# MCU_main.net
KiCad netlist of a schematic drawn in Altium Designer
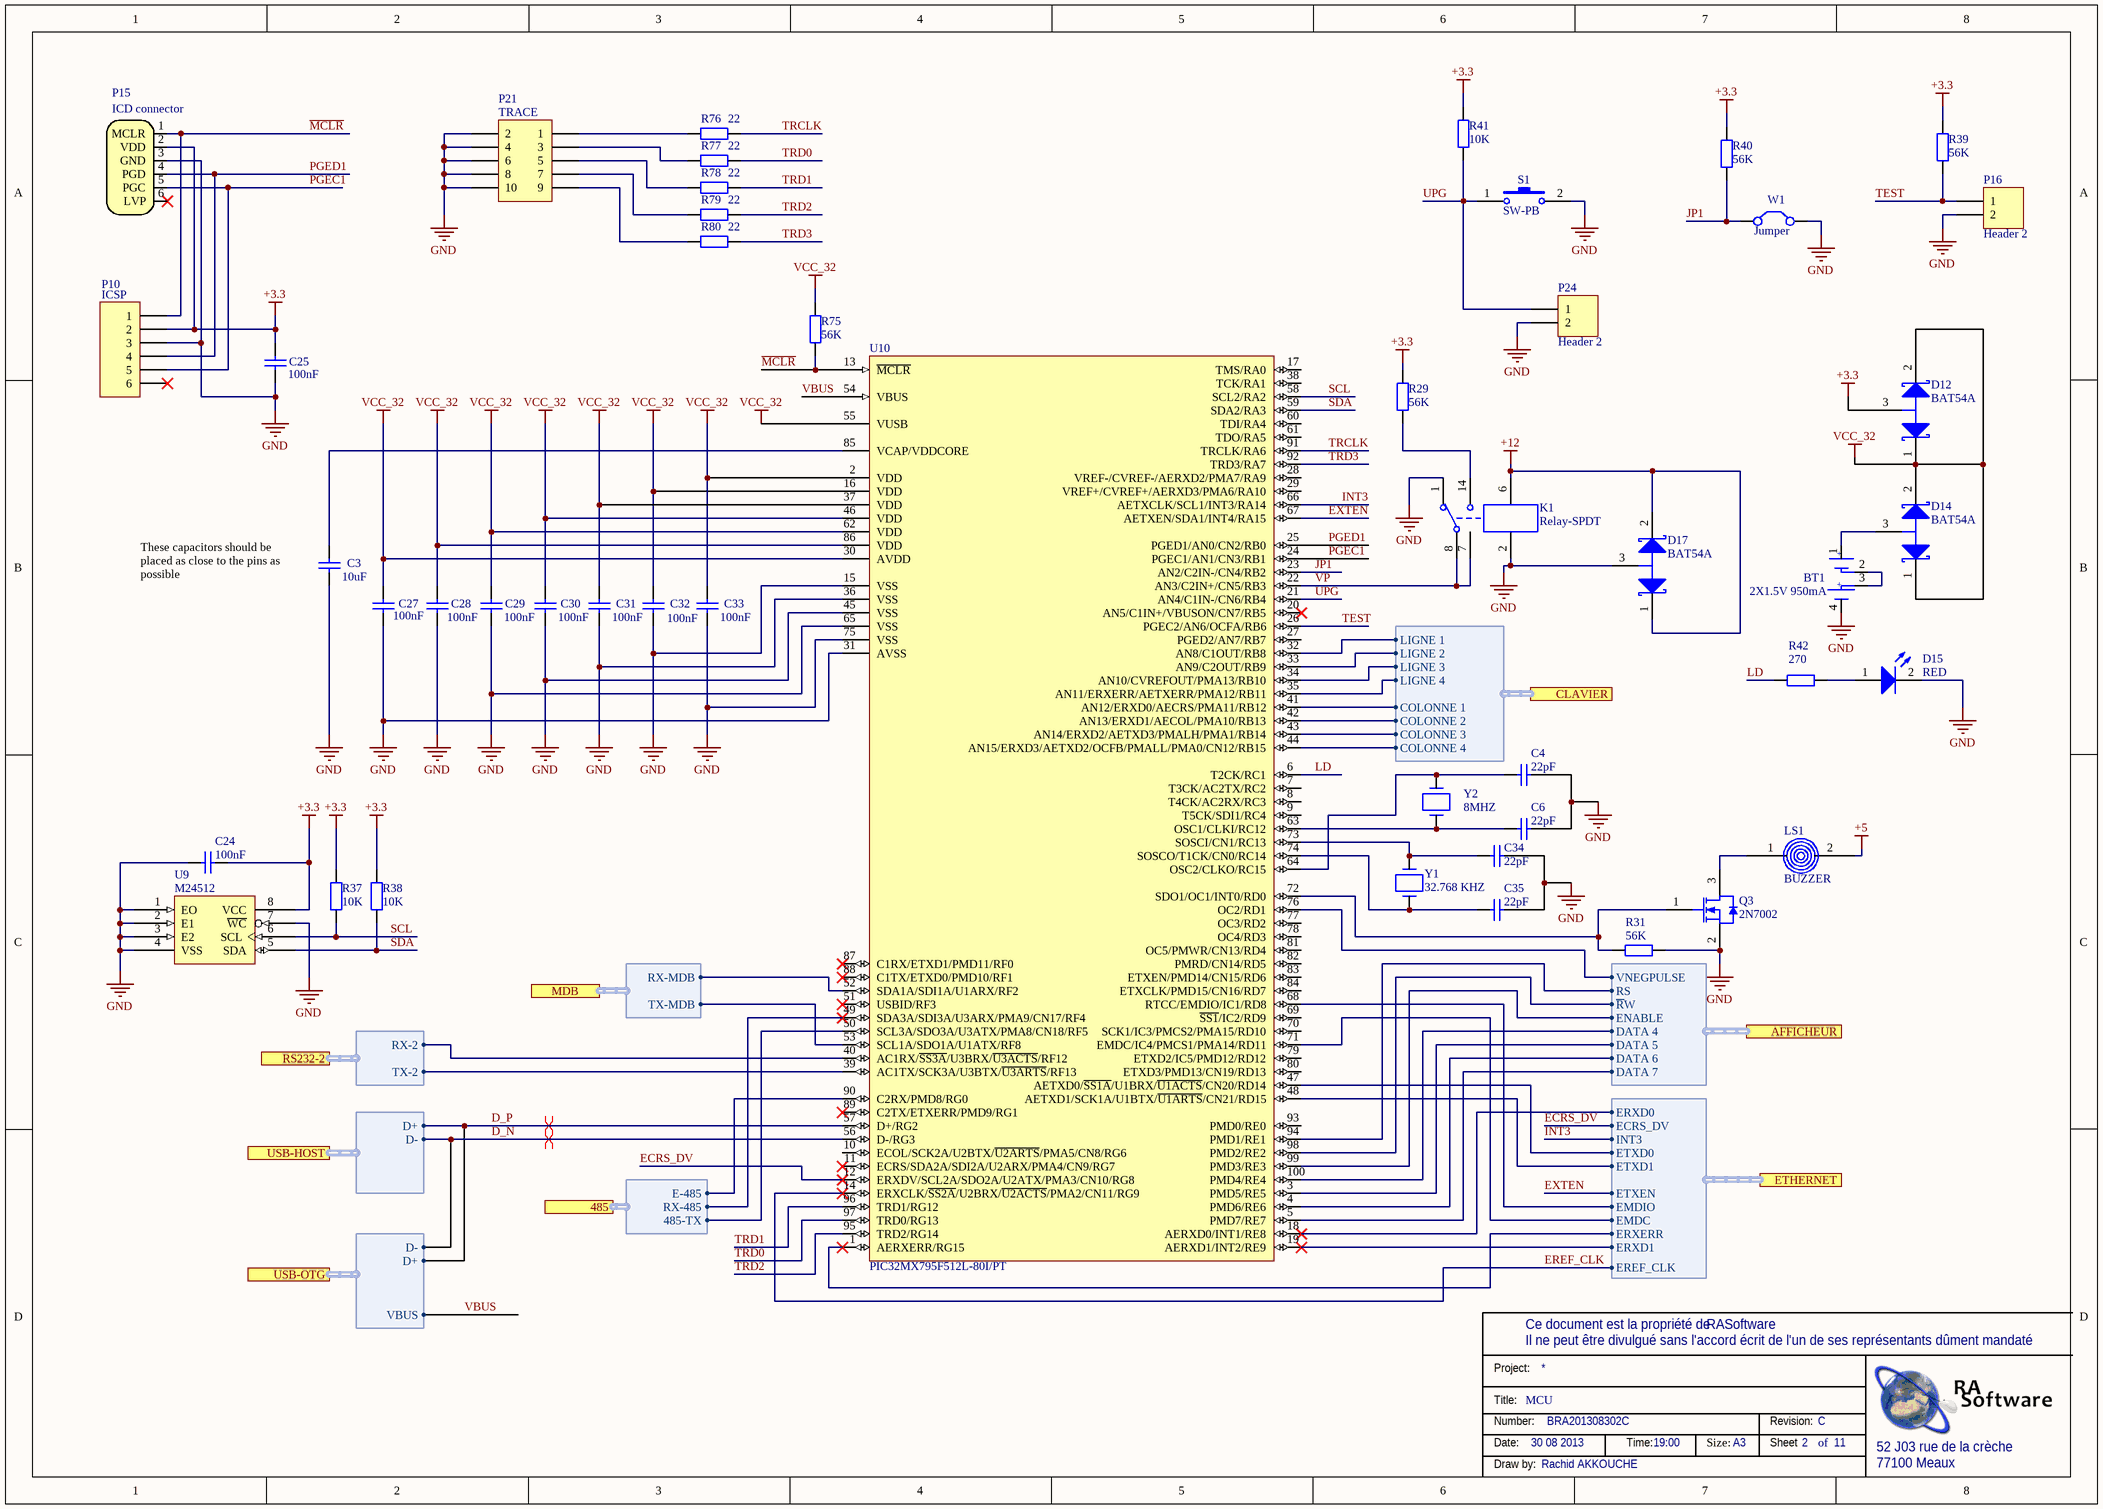
[diagram p0: MCU main.SchDoc]

(export (version "E")
  (design (tool "Eeschema 10.0.6"))
  (components
    (comp (ref "BT1")
      (value "2X1.5V 950mA")
      (footprint "Support Pile 1023")
      (libsource (lib "UTIL_Library") (part "BATTERYX2"))
    )
    (comp (ref "C3")
      (value "10uF")
      (footprint "c0805")
      (description "Capacitor")
      (fields
        (field (name "MANUFACTURER") "YAGEO")
        (field (name "MANUFACTURER PART NUMBER") "CC0805KKX5R5BB106")
      )
      (libsource (lib "BRA") (part "Cap 0805 1uF"))
    )
    (comp (ref "C4")
      (value "22pF")
      (footprint "C0805")
      (description "Capacitor")
      (fields
        (field (name "MANUFACTURER") "YAGEO")
        (field (name "MANUFACTURER PART NUMBER") "CC0805JRNPO9BN220")
      )
      (libsource (lib "BRA") (part "Cap 0805 22pF"))
    )
    (comp (ref "C6")
      (value "22pF")
      (footprint "C0805")
      (description "Capacitor")
      (fields
        (field (name "MANUFACTURER") "YAGEO")
        (field (name "MANUFACTURER PART NUMBER") "CC0805JRNPO9BN220")
      )
      (libsource (lib "BRA") (part "Cap 0805 22pF"))
    )
    (comp (ref "C24")
      (value "100nF")
      (footprint "C0805")
      (description "Capacitor")
      (fields
        (field (name "MANUFACTURER") "MULTICOMP")
        (field (name "MANUFACTURER PART NUMBER") "MCCA000296")
      )
      (libsource (lib "BRA") (part "Cap 0805 100nF"))
    )
    (comp (ref "C25")
      (value "100nF")
      (footprint "C0805")
      (description "Capacitor")
      (fields
        (field (name "MANUFACTURER") "MULTICOMP")
        (field (name "MANUFACTURER PART NUMBER") "MCCA000296")
      )
      (libsource (lib "BRA") (part "Cap 0805 100nF"))
    )
    (comp (ref "C27")
      (value "100nF")
      (footprint "C0805")
      (description "Capacitor")
      (fields
        (field (name "MANUFACTURER") "MULTICOMP")
        (field (name "MANUFACTURER PART NUMBER") "MCCA000296")
      )
      (libsource (lib "BRA") (part "Cap 0805 100nF"))
    )
    (comp (ref "C28")
      (value "100nF")
      (footprint "C0805")
      (description "Capacitor")
      (fields
        (field (name "MANUFACTURER") "MULTICOMP")
        (field (name "MANUFACTURER PART NUMBER") "MCCA000296")
      )
      (libsource (lib "BRA") (part "Cap 0805 100nF"))
    )
    (comp (ref "C29")
      (value "100nF")
      (footprint "C0805")
      (description "Capacitor")
      (fields
        (field (name "MANUFACTURER") "MULTICOMP")
        (field (name "MANUFACTURER PART NUMBER") "MCCA000296")
      )
      (libsource (lib "BRA") (part "Cap 0805 100nF"))
    )
    (comp (ref "C30")
      (value "100nF")
      (footprint "C0805")
      (description "Capacitor")
      (fields
        (field (name "MANUFACTURER") "MULTICOMP")
        (field (name "MANUFACTURER PART NUMBER") "MCCA000296")
      )
      (libsource (lib "BRA") (part "Cap 0805 100nF"))
    )
    (comp (ref "C31")
      (value "100nF")
      (footprint "C0805")
      (description "Capacitor")
      (fields
        (field (name "MANUFACTURER") "MULTICOMP")
        (field (name "MANUFACTURER PART NUMBER") "MCCA000296")
      )
      (libsource (lib "BRA") (part "Cap 0805 100nF"))
    )
    (comp (ref "C32")
      (value "100nF")
      (footprint "C0805")
      (description "Capacitor")
      (fields
        (field (name "MANUFACTURER") "MULTICOMP")
        (field (name "MANUFACTURER PART NUMBER") "MCCA000296")
      )
      (libsource (lib "BRA") (part "Cap 0805 100nF"))
    )
    (comp (ref "C33")
      (value "100nF")
      (footprint "C0805")
      (description "Capacitor")
      (fields
        (field (name "MANUFACTURER") "MULTICOMP")
        (field (name "MANUFACTURER PART NUMBER") "MCCA000296")
      )
      (libsource (lib "BRA") (part "Cap 0805 100nF"))
    )
    (comp (ref "C34")
      (value "22pF")
      (footprint "C0805")
      (description "Capacitor")
      (fields
        (field (name "MANUFACTURER") "YAGEO")
        (field (name "MANUFACTURER PART NUMBER") "CC0805JRNPO9BN220")
      )
      (libsource (lib "BRA") (part "Cap 0805 22pF"))
    )
    (comp (ref "C35")
      (value "22pF")
      (footprint "C0805")
      (description "Capacitor")
      (fields
        (field (name "MANUFACTURER") "YAGEO")
        (field (name "MANUFACTURER PART NUMBER") "CC0805JRNPO9BN220")
      )
      (libsource (lib "BRA") (part "Cap 0805 22pF"))
    )
    (comp (ref "D12")
      (value "BAT54A")
      (footprint "SOT23")
      (description "Schottky Barrier Double Diode")
      (fields (field (name "MANUFACTURER") "FAIRCHILD SEMICONDUCTOR"))
      (libsource (lib "Philips Discrete Diode - Schottky") (part "BAT54A"))
    )
    (comp (ref "D14")
      (value "BAT54A")
      (footprint "SOT23")
      (description "Schottky Barrier Double Diode")
      (fields (field (name "MANUFACTURER") "FAIRCHILD SEMICONDUCTOR"))
      (libsource (lib "Philips Discrete Diode - Schottky") (part "BAT54A"))
    )
    (comp (ref "D15")
      (value "HSMH-C190")
      (footprint "SYLANN:0603-LEDR")
      (description "Surface Mount Chip LED, Red")
      (fields
        (field (name "MANUFACTURER") "AVAGO TECHNOLOGIES")
        (field (name "MANUFACTURER PART NUMBER") "HSMH-C190.")
        (field (name "COULEUR") "RED")
        (field (name "LONGUEUR/HAUTEUR") "1.6")
      )
      (libsource (lib "Avago Optoelectronic LED") (part "HSMH-C190"))
    )
    (comp (ref "D17")
      (value "BAT54A")
      (footprint "SOT23")
      (description "Schottky Barrier Double Diode")
      (fields (field (name "MANUFACTURER") "FAIRCHILD SEMICONDUCTOR"))
      (libsource (lib "Philips Discrete Diode - Schottky") (part "BAT54A"))
    )
    (comp (ref "K1")
      (value "Relay-SPDT")
      (footprint "RELE-REED-PVX6012")
      (description "Single-Pole Dual-Throw Relay")
      (fields
        (field (name "MANUFACTURER") "STANDEXMEDER")
        (field (name "MANUFACTURER PART NUMBER") "DIP12-1C90-51L")
        (field (name "PUBLISHER") "Altium Limited")
      )
      (libsource (lib "MAIN BOARD CERES_1") (part "Relay-SPDT"))
    )
    (comp (ref "LS1")
      (value "BUZZER")
      (description "SMD magnetic transducter buzzer")
      (fields
        (field (name "MANUFACTURER") "Pro Signal")
        (field (name "MANUFACTURER PART NUMBER") "ABI-017-RC")
      )
      (libsource (lib "BRA") (part "ABI-017-RC"))
    )
    (comp (ref "P10")
      (value "M20-8770642")
      (footprint "M20_1X6")
      (description "Header, 6-Pin")
      (fields (field (name "MANUFACTURER") "HARWIN") (field (name "ALTIUM_UNNAMED_1") "ICSP"))
      (libsource (lib "Miscellaneous Connectors") (part "Header 6"))
    )
    (comp (ref "P15")
      (value "ICD connector")
      (footprint "TC2030")
      (description "Conector par ICD")
      (libsource (lib "TC2030") (part "TC2030-MCP-NL"))
    )
    (comp (ref "P16")
      (value "Header 2")
      (footprint "M20_1X2")
      (description "Header, 2-Pin")
      (fields
        (field (name "MANUFACTURER") "HARWIN")
        (field (name "MANUFACTURER PART NUMBER") "M20-8770242")
        (field (name "PUBLISHER") "Altium Limited")
      )
      (libsource (lib "Miscellaneous Connectors") (part "Header 2"))
    )
    (comp (ref "P21")
      (value "M20-8760542")
      (footprint "HE10_10PTS_CMS")
      (description "Header, 5-Pin, Dual row")
      (fields (field (name "ALTIUM_UNNAMED_1") "TRACE") (field (name "MANUFACTURER") "HARWIN"))
      (libsource (lib "Miscellaneous Connectors") (part "Header 5X2"))
    )
    (comp (ref "P24")
      (value "Header 2")
      (footprint "M20_1X2")
      (description "Header, 2-Pin")
      (fields
        (field (name "MANUFACTURER") "HARWIN")
        (field (name "MANUFACTURER PART NUMBER") "M20-8770242")
        (field (name "PUBLISHER") "Altium Limited")
      )
      (libsource (lib "Miscellaneous Connectors") (part "Header 2"))
    )
    (comp (ref "Q3")
      (value "2N7002")
      (footprint "SOT23")
      (description "N-channel Enhancement Mode Field-effect Transistor")
      (fields (field (name "MANUFACTURER") "STMICROELECTRONICS") (field (name "PUBLISHER") "Altium Limited"))
      (libsource (lib "Philips Discrete MOSFET - Low Power") (part "2N7002"))
    )
    (comp (ref "R29")
      (value "56K")
      (footprint "R0805")
      (description "Resistor")
      (fields
        (field (name "MANUFACTURER") "MULTICOMP")
        (field (name "MANUFACTURER PART NUMBER") "MC0.1W08051%56KFR")
      )
      (libsource (lib "") (part "Resistor 0805 56K_1"))
    )
    (comp (ref "R31")
      (value "56K")
      (footprint "R0805")
      (description "Resistor")
      (fields
        (field (name "MANUFACTURER") "MULTICOMP")
        (field (name "MANUFACTURER PART NUMBER") "MC0.1W08051%56KFR")
      )
      (libsource (lib "BRA") (part "Resistor 0805 56K"))
    )
    (comp (ref "R37")
      (value "10K")
      (footprint "R0805")
      (description "Resistor")
      (fields
        (field (name "MANUFACTURER") "MULTICOMP")
        (field (name "MANUFACTURER PART NUMBER") "MC0.1W08051%10KFR")
      )
      (libsource (lib "BRA") (part "Resistor 0805 10K"))
    )
    (comp (ref "R38")
      (value "10K")
      (footprint "R0805")
      (description "Resistor")
      (fields
        (field (name "MANUFACTURER") "MULTICOMP")
        (field (name "MANUFACTURER PART NUMBER") "MC0.1W08051%10KFR")
      )
      (libsource (lib "BRA") (part "Resistor 0805 10K"))
    )
    (comp (ref "R39")
      (value "56K")
      (footprint "R0805")
      (description "Resistor")
      (fields
        (field (name "MANUFACTURER") "MULTICOMP")
        (field (name "MANUFACTURER PART NUMBER") "MC0.1W08051%56KFR")
      )
      (libsource (lib "") (part "Resistor 0805 56K_1"))
    )
    (comp (ref "R40")
      (value "56K")
      (footprint "R0805")
      (description "Resistor")
      (fields
        (field (name "MANUFACTURER") "MULTICOMP")
        (field (name "MANUFACTURER PART NUMBER") "MC0.1W08051%56KFR")
      )
      (libsource (lib "") (part "Resistor 0805 56K_1"))
    )
    (comp (ref "R41")
      (value "10K")
      (footprint "R0805")
      (description "Resistor")
      (fields
        (field (name "MANUFACTURER") "MULTICOMP")
        (field (name "MANUFACTURER PART NUMBER") "MC0.1W08051%10KFR")
      )
      (libsource (lib "BRA") (part "Resistor 0805 10K"))
    )
    (comp (ref "R42")
      (value "270")
      (footprint "R0805")
      (description "Resistor")
      (fields
        (field (name "MANUFACTURER") "MULTICOMP")
        (field (name "MANUFACTURER PART NUMBER") "MC0.1W08051%1KFR")
      )
      (libsource (lib "BRA") (part "Resistor 0805 1K"))
    )
    (comp (ref "R75")
      (value "56K")
      (footprint "R0805")
      (description "Resistor")
      (fields
        (field (name "MANUFACTURER") "MULTICOMP")
        (field (name "MANUFACTURER PART NUMBER") "MC0.1W08051%56KFR")
      )
      (libsource (lib "") (part "Resistor 0805 56K_1"))
    )
    (comp (ref "R76")
      (value "22")
      (footprint "R0805")
      (description "Resistor")
      (fields
        (field (name "MANUFACTURER") "MULTICOMP")
        (field (name "MANUFACTURER PART NUMBER") "MC01W0805122R")
      )
      (libsource (lib "BRA") (part "Resistor 0805 22"))
    )
    (comp (ref "R77")
      (value "22")
      (footprint "R0805")
      (description "Resistor")
      (fields
        (field (name "MANUFACTURER") "MULTICOMP")
        (field (name "MANUFACTURER PART NUMBER") "MC01W0805122R")
      )
      (libsource (lib "BRA") (part "Resistor 0805 22"))
    )
    (comp (ref "R78")
      (value "22")
      (footprint "R0805")
      (description "Resistor")
      (fields
        (field (name "MANUFACTURER") "MULTICOMP")
        (field (name "MANUFACTURER PART NUMBER") "MC01W0805122R")
      )
      (libsource (lib "BRA") (part "Resistor 0805 22"))
    )
    (comp (ref "R79")
      (value "22")
      (footprint "R0805")
      (description "Resistor")
      (fields
        (field (name "MANUFACTURER") "MULTICOMP")
        (field (name "MANUFACTURER PART NUMBER") "MC01W0805122R")
      )
      (libsource (lib "BRA") (part "Resistor 0805 22"))
    )
    (comp (ref "R80")
      (value "22")
      (footprint "R0805")
      (description "Resistor")
      (fields
        (field (name "MANUFACTURER") "MULTICOMP")
        (field (name "MANUFACTURER PART NUMBER") "MC01W0805122R")
      )
      (libsource (lib "BRA") (part "Resistor 0805 22"))
    )
    (comp (ref "S1")
      (value "SW-PB")
      (footprint "EVQQ2Y03W")
      (description "Switch")
      (fields
        (field (name "MANUFACTURER") "PANASONIC")
        (field (name "MANUFACTURER PART NUMBER") "EVQQ2Y03W")
        (field (name "PUBLISHER") "Altium Limited")
      )
      (libsource (lib "Miscellaneous Devices") (part "SW-PB"))
    )
    (comp (ref "U9")
      (value "M24512")
      (footprint "SOIC8")
      (description "EEPROM 512K I2C")
      (fields
        (field (name "MANUFACTURER") "STMICROELECTRONICS")
        (field (name "MANUFACTURER PART NUMBER") "M24512-WMN6P")
      )
      (libsource (lib "BRA") (part "M24512-MN"))
    )
    (comp (ref "U10")
      (value "PIC32MX795F512L-80I/PT")
      (footprint "TQFP100pt")
      (fields (field (name "PUBLISHER") "Altium Limited"))
      (libsource (lib "Microchip Microcontroller 32-Bit PIC32") (part "PIC32MX795F512L-80I/PT"))
    )
    (comp (ref "W1")
      (value "Jumper")
      (footprint "M20_1X2")
      (description "Jumper Wire")
      (fields
        (field (name "MANUFACTURER") "HARWIN")
        (field (name "MANUFACTURER PART NUMBER") "M20-8770242")
        (field (name "PUBLISHER") "Altium Limited")
      )
      (libsource (lib "Miscellaneous Devices") (part "Jumper"))
    )
    (comp (ref "Y1")
      (value "32.768 KHZ")
      (footprint "FSRLF")
      (fields
        (field (name "MANUFACTURER") "FOX ELECTRONICS")
        (field (name "MANUFACTURER PART NUMBER") "FSRLF327.")
      )
      (libsource (lib "UTIL_Library") (part "CRYSTAL2"))
    )
    (comp (ref "Y2")
      (value "8MHZ")
      (footprint "86SMX")
      (fields
        (field (name "MANUFACTURER") "FOX ELECTRONICS")
        (field (name "MANUFACTURER PART NUMBER") "FPXLF080-20")
      )
      (libsource (lib "UTIL_Library") (part "CRYSTAL2"))
    )
  )
  (nets
    (net (code "10") (name "+3.3") (class "Default")
      (node (ref "C24") (pin "1") (pinfunction "1_1") (pintype "passive"))
      (node (ref "C25") (pin "2") (pinfunction "2_2") (pintype "passive"))
      (node (ref "D12") (pin "3") (pinfunction "A_3") (pintype "passive"))
      (node (ref "P10") (pin "2") (pinfunction "2_2") (pintype "passive"))
      (node (ref "P15") (pin "2") (pinfunction "VDD_2") (pintype "passive"))
      (node (ref "R29") (pin "2") (pinfunction "2_2") (pintype "passive"))
      (node (ref "R37") (pin "2") (pinfunction "2_2") (pintype "passive"))
      (node (ref "R38") (pin "2") (pinfunction "2_2") (pintype "passive"))
      (node (ref "R39") (pin "2") (pinfunction "2_2") (pintype "passive"))
      (node (ref "R40") (pin "2") (pinfunction "2_2") (pintype "passive"))
      (node (ref "R41") (pin "2") (pinfunction "2_2") (pintype "passive"))
      (node (ref "U9") (pin "8") (pinfunction "VCC_8") (pintype "power_in"))
    )
    (net (code "11") (name "+5") (class "Default")
      (node (ref "LS1") (pin "2") (pinfunction "GND_2") (pintype "power_in"))
    )
    (net (code "12") (name "+12") (class "Default")
      (node (ref "D17") (pin "1") (pinfunction "K1_1") (pintype "passive"))
      (node (ref "D17") (pin "2") (pinfunction "K2_2") (pintype "passive"))
      (node (ref "K1") (pin "6") (pinfunction "6_6") (pintype "passive"))
    )
    (net (code "13") (name "/485-TX") (class "Default")
      (node (ref "U10") (pin "50") (pinfunction "SCL3A/SDO3A/U3ATX/PMA8/CN18/RF5_50") (pintype "bidirectional"))
    )
    (net (code "14") (name "/COLONNE 1") (class "Default")
      (node (ref "U10") (pin "41") (pinfunction "AN12/ERXD0/AECRS/PMA11/RB12_41") (pintype "bidirectional"))
    )
    (net (code "15") (name "/COLONNE 2") (class "Default")
      (node (ref "U10") (pin "42") (pinfunction "AN13/ERXD1/AECOL/PMA10/RB13_42") (pintype "bidirectional"))
    )
    (net (code "16") (name "/COLONNE 3") (class "Default")
      (node (ref "U10") (pin "43") (pinfunction "AN14/ERXD2/AETXD3/PMALH/PMA1/RB14_43") (pintype "bidirectional"))
    )
    (net (code "17") (name "/COLONNE 4") (class "Default")
      (node (ref "U10") (pin "44") (pinfunction "AN15/ERXD3/AETXD2/OCFB/PMALL/PMA0/CN12/RB15_44") (pintype "bidirectional"))
    )
    (net (code "18") (name "/DATA 4") (class "Default")
      (node (ref "U10") (pin "100") (pinfunction "PMD4/RE4_100") (pintype "bidirectional"))
    )
    (net (code "19") (name "/DATA 5") (class "Default")
      (node (ref "U10") (pin "3") (pinfunction "PMD5/RE5_3") (pintype "bidirectional"))
    )
    (net (code "20") (name "/DATA 6") (class "Default")
      (node (ref "U10") (pin "4") (pinfunction "PMD6/RE6_4") (pintype "bidirectional"))
    )
    (net (code "21") (name "/DATA 7") (class "Default")
      (node (ref "U10") (pin "5") (pinfunction "PMD7/RE7_5") (pintype "bidirectional"))
    )
    (net (code "22") (name "/D_N") (class "Default")
      (node (ref "U10") (pin "56") (pinfunction "D-/RG3_56") (pintype "bidirectional"))
    )
    (net (code "23") (name "/D_P") (class "Default")
      (node (ref "U10") (pin "57") (pinfunction "D+/RG2_57") (pintype "bidirectional"))
    )
    (net (code "24") (name "/E-485") (class "Default")
      (node (ref "U10") (pin "90") (pinfunction "C2RX/PMD8/RG0_90") (pintype "bidirectional"))
    )
    (net (code "25") (name "/ECRS_DV") (class "Default")
      (node (ref "U10") (pin "12") (pinfunction "ERXDV/SCL2A/SDO2A/U2ATX/PMA3/CN10/RG8_12") (pintype "bidirectional"))
    )
    (net (code "26") (name "/EMDC") (class "Default")
      (node (ref "U10") (pin "71") (pinfunction "EMDC/IC4/PMCS1/PMA14/RD11_71") (pintype "bidirectional"))
    )
    (net (code "27") (name "/EMDIO") (class "Default")
      (node (ref "U10") (pin "68") (pinfunction "RTCC/EMDIO/IC1/RD8_68") (pintype "bidirectional"))
    )
    (net (code "28") (name "/ENABLE") (class "Default")
      (node (ref "U10") (pin "99") (pinfunction "PMD3/RE3_99") (pintype "bidirectional"))
    )
    (net (code "29") (name "/EREF_CLK") (class "Default")
      (node (ref "U10") (pin "14") (pinfunction "ERXCLK/~{SS2A}/U2BRX/~{U2ACTS}/PMA2/CN11/RG9_14") (pintype "bidirectional+no_connect"))
    )
    (net (code "30") (name "/ERXD0") (class "Default")
      (node (ref "U10") (pin "18") (pinfunction "AERXD0/INT1/RE8_18") (pintype "bidirectional+no_connect"))
    )
    (net (code "31") (name "/ERXD1") (class "Default")
      (node (ref "U10") (pin "19") (pinfunction "AERXD1/INT2/RE9_19") (pintype "bidirectional+no_connect"))
    )
    (net (code "32") (name "/ERXERR") (class "Default")
      (node (ref "U10") (pin "1") (pinfunction "AERXERR/RG15_1") (pintype "bidirectional+no_connect"))
    )
    (net (code "33") (name "/ETXD0") (class "Default")
      (node (ref "U10") (pin "47") (pinfunction "AETXD0/~{SS1A}/U1BRX/~{U1ACTS}/CN20/RD14_47") (pintype "bidirectional"))
    )
    (net (code "34") (name "/ETXD1") (class "Default")
      (node (ref "U10") (pin "48") (pinfunction "AETXD1/SCK1A/U1BTX/~{U1ARTS}/CN21/RD15_48") (pintype "bidirectional"))
    )
    (net (code "35") (name "/EXTEN") (class "Default")
      (node (ref "U10") (pin "67") (pinfunction "AETXEN/SDA1/INT4/RA15_67") (pintype "bidirectional"))
    )
    (net (code "36") (name "/INT3") (class "Default")
      (node (ref "U10") (pin "66") (pinfunction "AETXCLK/SCL1/INT3/RA14_66") (pintype "bidirectional"))
    )
    (net (code "37") (name "/JP1") (class "Default")
      (node (ref "R40") (pin "1") (pinfunction "1_1") (pintype "passive"))
      (node (ref "U10") (pin "23") (pinfunction "AN2/C2IN-/CN4/RB2_23") (pintype "bidirectional"))
      (node (ref "W1") (pin "1") (pinfunction "C1_1") (pintype "passive"))
    )
    (net (code "38") (name "/LD") (class "Default")
      (node (ref "R42") (pin "2") (pinfunction "2_2") (pintype "passive"))
      (node (ref "U10") (pin "6") (pinfunction "T2CK/RC1_6") (pintype "bidirectional"))
    )
    (net (code "39") (name "/LIGNE 1") (class "Default")
      (node (ref "U10") (pin "32") (pinfunction "AN8/C1OUT/RB8_32") (pintype "bidirectional"))
    )
    (net (code "40") (name "/LIGNE 2") (class "Default")
      (node (ref "U10") (pin "33") (pinfunction "AN9/C2OUT/RB9_33") (pintype "bidirectional"))
    )
    (net (code "41") (name "/LIGNE 3") (class "Default")
      (node (ref "U10") (pin "34") (pinfunction "AN10/CVREFOUT/PMA13/RB10_34") (pintype "bidirectional"))
    )
    (net (code "42") (name "/LIGNE 4") (class "Default")
      (node (ref "U10") (pin "35") (pinfunction "AN11/ERXERR/AETXERR/PMA12/RB11_35") (pintype "bidirectional"))
    )
    (net (code "43") (name "/PGEC1") (class "Default")
      (node (ref "P10") (pin "5") (pinfunction "5_5") (pintype "passive"))
      (node (ref "P15") (pin "5") (pinfunction "PGC_5") (pintype "passive"))
      (node (ref "U10") (pin "24") (pinfunction "PGEC1/AN1/CN3/RB1_24") (pintype "bidirectional"))
    )
    (net (code "44") (name "/PGED1") (class "Default")
      (node (ref "P10") (pin "4") (pinfunction "4_4") (pintype "passive"))
      (node (ref "P15") (pin "4") (pinfunction "PGD_4") (pintype "passive"))
      (node (ref "U10") (pin "25") (pinfunction "PGED1/AN0/CN2/RB0_25") (pintype "bidirectional"))
    )
    (net (code "45") (name "/RS") (class "Default")
      (node (ref "U10") (pin "94") (pinfunction "PMD1/RE1_94") (pintype "bidirectional"))
    )
    (net (code "46") (name "/RX-2") (class "Default")
      (node (ref "U10") (pin "40") (pinfunction "AC1RX/~{SS3A}/U3BRX/~{U3ACTS}/RF12_40") (pintype "bidirectional"))
    )
    (net (code "47") (name "/RX-485") (class "Default")
      (node (ref "U10") (pin "49") (pinfunction "SDA3A/SDI3A/U3ARX/PMA9/CN17/RF4_49") (pintype "bidirectional+no_connect"))
    )
    (net (code "48") (name "/RX-MDB") (class "Default")
      (node (ref "U10") (pin "52") (pinfunction "SDA1A/SDI1A/U1ARX/RF2_52") (pintype "bidirectional"))
    )
    (net (code "49") (name "/SCL") (class "Default")
      (node (ref "R37") (pin "1") (pinfunction "1_1") (pintype "passive"))
      (node (ref "U10") (pin "58") (pinfunction "SCL2/RA2_58") (pintype "bidirectional"))
      (node (ref "U9") (pin "6") (pinfunction "SCL_6") (pintype "input"))
    )
    (net (code "50") (name "/SDA") (class "Default")
      (node (ref "R38") (pin "1") (pinfunction "1_1") (pintype "passive"))
      (node (ref "U10") (pin "59") (pinfunction "SDA2/RA3_59") (pintype "bidirectional"))
      (node (ref "U9") (pin "5") (pinfunction "SDA_5") (pintype "bidirectional"))
    )
    (net (code "51") (name "/TEST") (class "Default")
      (node (ref "P16") (pin "1") (pinfunction "1_1") (pintype "passive"))
      (node (ref "R39") (pin "1") (pinfunction "1_1") (pintype "passive"))
      (node (ref "U10") (pin "26") (pinfunction "PGEC2/AN6/OCFA/RB6_26") (pintype "bidirectional"))
    )
    (net (code "52") (name "/TRCLK") (class "Default")
      (node (ref "R76") (pin "1") (pinfunction "1_1") (pintype "passive"))
      (node (ref "U10") (pin "91") (pinfunction "TRCLK/RA6_91") (pintype "bidirectional"))
    )
    (net (code "53") (name "/TRD0") (class "Default")
      (node (ref "R77") (pin "1") (pinfunction "1_1") (pintype "passive"))
      (node (ref "U10") (pin "97") (pinfunction "TRD0/RG13_97") (pintype "bidirectional"))
    )
    (net (code "54") (name "/TRD1") (class "Default")
      (node (ref "R78") (pin "1") (pinfunction "1_1") (pintype "passive"))
      (node (ref "U10") (pin "96") (pinfunction "TRD1/RG12_96") (pintype "bidirectional"))
    )
    (net (code "55") (name "/TRD2") (class "Default")
      (node (ref "R79") (pin "1") (pinfunction "1_1") (pintype "passive"))
      (node (ref "U10") (pin "95") (pinfunction "TRD2/RG14_95") (pintype "bidirectional"))
    )
    (net (code "56") (name "/TRD3") (class "Default")
      (node (ref "R80") (pin "1") (pinfunction "1_1") (pintype "passive"))
      (node (ref "U10") (pin "92") (pinfunction "TRD3/RA7_92") (pintype "bidirectional"))
    )
    (net (code "57") (name "/TX-2") (class "Default")
      (node (ref "U10") (pin "39") (pinfunction "AC1TX/SCK3A/U3BTX/~{U3ARTS}/RF13_39") (pintype "bidirectional"))
    )
    (net (code "58") (name "/TX-MDB") (class "Default")
      (node (ref "U10") (pin "53") (pinfunction "SCL1A/SDO1A/U1ATX/RF8_53") (pintype "bidirectional"))
    )
    (net (code "59") (name "/UPG") (class "Default")
      (node (ref "P24") (pin "1") (pinfunction "1_1") (pintype "passive"))
      (node (ref "R41") (pin "1") (pinfunction "1_1") (pintype "passive"))
      (node (ref "S1") (pin "1") (pinfunction "1_1") (pintype "passive"))
      (node (ref "U10") (pin "21") (pinfunction "AN4/C1IN-/CN6/RB4_21") (pintype "bidirectional"))
    )
    (net (code "60") (name "/VBUS") (class "Default")
      (node (ref "U10") (pin "54") (pinfunction "VBUS_54") (pintype "input"))
    )
    (net (code "61") (name "/VNEGPULSE") (class "Default")
      (node (ref "U10") (pin "76") (pinfunction "OC2/RD1_76") (pintype "bidirectional"))
    )
    (net (code "62") (name "/VP") (class "Default")
      (node (ref "K1") (pin "7") (pinfunction "7_7") (pintype "passive"))
      (node (ref "K1") (pin "8") (pinfunction "8_8") (pintype "passive"))
      (node (ref "U10") (pin "22") (pinfunction "AN3/C2IN+/CN5/RB3_22") (pintype "bidirectional"))
    )
    (net (code "71") (name "/~{MCLR}") (class "Default")
      (node (ref "P10") (pin "1") (pinfunction "1_1") (pintype "passive"))
      (node (ref "P15") (pin "1") (pinfunction "MCLR_1") (pintype "passive"))
      (node (ref "R75") (pin "1") (pinfunction "1_1") (pintype "passive"))
      (node (ref "U10") (pin "13") (pinfunction "~{MCLR}_13") (pintype "input"))
    )
    (net (code "72") (name "/~{R}W") (class "Default")
      (node (ref "U10") (pin "98") (pinfunction "PMD2/RE2_98") (pintype "bidirectional"))
    )
    (net (code "73") (name "GND") (class "Default")
      (node (ref "BT1") (pin "4") (pinfunction "4_4") (pintype "passive"))
      (node (ref "C24") (pin "2") (pinfunction "2_2") (pintype "passive"))
      (node (ref "C25") (pin "1") (pinfunction "1_1") (pintype "passive"))
      (node (ref "C27") (pin "1") (pinfunction "1_1") (pintype "passive"))
      (node (ref "C28") (pin "1") (pinfunction "1_1") (pintype "passive"))
      (node (ref "C29") (pin "1") (pinfunction "1_1") (pintype "passive"))
      (node (ref "C3") (pin "2") (pinfunction "2_2") (pintype "passive"))
      (node (ref "C30") (pin "1") (pinfunction "1_1") (pintype "passive"))
      (node (ref "C31") (pin "1") (pinfunction "1_1") (pintype "passive"))
      (node (ref "C32") (pin "1") (pinfunction "1_1") (pintype "passive"))
      (node (ref "C33") (pin "1") (pinfunction "1_1") (pintype "passive"))
      (node (ref "C34") (pin "1") (pinfunction "1_1") (pintype "passive"))
      (node (ref "C35") (pin "1") (pinfunction "1_1") (pintype "passive"))
      (node (ref "C4") (pin "1") (pinfunction "1_1") (pintype "passive"))
      (node (ref "C6") (pin "1") (pinfunction "1_1") (pintype "passive"))
      (node (ref "D15") (pin "2") (pinfunction "K_2") (pintype "passive"))
      (node (ref "D17") (pin "3") (pinfunction "A_3") (pintype "passive"))
      (node (ref "K1") (pin "1") (pinfunction "1_1") (pintype "passive"))
      (node (ref "K1") (pin "2") (pinfunction "2_2") (pintype "passive"))
      (node (ref "P10") (pin "3") (pinfunction "3_3") (pintype "passive"))
      (node (ref "P15") (pin "3") (pinfunction "GND_3") (pintype "passive"))
      (node (ref "P16") (pin "2") (pinfunction "2_2") (pintype "passive"))
      (node (ref "P21") (pin "10") (pinfunction "10_10") (pintype "passive"))
      (node (ref "P21") (pin "2") (pinfunction "2_2") (pintype "passive"))
      (node (ref "P21") (pin "4") (pinfunction "4_4") (pintype "passive"))
      (node (ref "P21") (pin "6") (pinfunction "6_6") (pintype "passive"))
      (node (ref "P21") (pin "8") (pinfunction "8_8") (pintype "passive"))
      (node (ref "P24") (pin "2") (pinfunction "2_2") (pintype "passive"))
      (node (ref "Q3") (pin "2") (pinfunction "S_2") (pintype "passive"))
      (node (ref "R31") (pin "1") (pinfunction "1_1") (pintype "passive"))
      (node (ref "S1") (pin "2") (pinfunction "2_2") (pintype "passive"))
      (node (ref "U10") (pin "15") (pinfunction "VSS_15") (pintype "power_in"))
      (node (ref "U10") (pin "31") (pinfunction "AVSS_31") (pintype "power_in"))
      (node (ref "U10") (pin "36") (pinfunction "VSS_36") (pintype "power_in"))
      (node (ref "U10") (pin "45") (pinfunction "VSS_45") (pintype "power_in"))
      (node (ref "U10") (pin "65") (pinfunction "VSS_65") (pintype "power_in"))
      (node (ref "U10") (pin "75") (pinfunction "VSS_75") (pintype "power_in"))
      (node (ref "U9") (pin "1") (pinfunction "EO_1") (pintype "input"))
      (node (ref "U9") (pin "2") (pinfunction "E1_2") (pintype "input"))
      (node (ref "U9") (pin "3") (pinfunction "E2_3") (pintype "input"))
      (node (ref "U9") (pin "4") (pinfunction "VSS_4") (pintype "power_in"))
      (node (ref "U9") (pin "7") (pinfunction "~{WC}_7") (pintype "input"))
      (node (ref "W1") (pin "2") (pinfunction "C2_2") (pintype "passive"))
    )
    (net (code "74") (name "Net-(BT1-+)") (class "Default")
      (node (ref "BT1") (pin "1") (pinfunction "+_1") (pintype "passive"))
      (node (ref "D14") (pin "3") (pinfunction "A_3") (pintype "passive"))
    )
    (net (code "75") (name "Net-(BT1-Pad2)") (class "Default")
      (node (ref "BT1") (pin "2") (pinfunction "2_2") (pintype "passive"))
      (node (ref "BT1") (pin "3") (pinfunction "3_3") (pintype "passive"))
    )
    (net (code "76") (name "Net-(D15-A)") (class "Default")
      (node (ref "D15") (pin "1") (pinfunction "A_1") (pintype "passive"))
      (node (ref "R42") (pin "1") (pinfunction "1_1") (pintype "passive"))
    )
    (net (code "77") (name "Net-(K1-Pad14)") (class "Default")
      (node (ref "K1") (pin "14") (pinfunction "14_14") (pintype "passive"))
      (node (ref "R29") (pin "1") (pinfunction "1_1") (pintype "passive"))
    )
    (net (code "78") (name "Net-(LS1-+)") (class "Default")
      (node (ref "LS1") (pin "1") (pinfunction "+_1") (pintype "power_in"))
      (node (ref "Q3") (pin "3") (pinfunction "D_3") (pintype "passive"))
    )
    (net (code "79") (name "Net-(P21-Pad1)") (class "Default")
      (node (ref "P21") (pin "1") (pinfunction "1_1") (pintype "passive"))
      (node (ref "R76") (pin "2") (pinfunction "2_2") (pintype "passive"))
    )
    (net (code "80") (name "Net-(P21-Pad3)") (class "Default")
      (node (ref "P21") (pin "3") (pinfunction "3_3") (pintype "passive"))
      (node (ref "R77") (pin "2") (pinfunction "2_2") (pintype "passive"))
    )
    (net (code "81") (name "Net-(P21-Pad5)") (class "Default")
      (node (ref "P21") (pin "5") (pinfunction "5_5") (pintype "passive"))
      (node (ref "R78") (pin "2") (pinfunction "2_2") (pintype "passive"))
    )
    (net (code "82") (name "Net-(P21-Pad7)") (class "Default")
      (node (ref "P21") (pin "7") (pinfunction "7_7") (pintype "passive"))
      (node (ref "R79") (pin "2") (pinfunction "2_2") (pintype "passive"))
    )
    (net (code "83") (name "Net-(P21-Pad9)") (class "Default")
      (node (ref "P21") (pin "9") (pinfunction "9_9") (pintype "passive"))
      (node (ref "R80") (pin "2") (pinfunction "2_2") (pintype "passive"))
    )
    (net (code "84") (name "Net-(Q3-G)") (class "Default")
      (node (ref "Q3") (pin "1") (pinfunction "G_1") (pintype "passive"))
      (node (ref "R31") (pin "2") (pinfunction "2_2") (pintype "passive"))
      (node (ref "U10") (pin "72") (pinfunction "SDO1/OC1/INT0/RD0_72") (pintype "bidirectional"))
    )
    (net (code "85") (name "Net-(U10-OSC1{slash}CLKI{slash}RC12)") (class "Default")
      (node (ref "C6") (pin "2") (pinfunction "2_2") (pintype "passive"))
      (node (ref "U10") (pin "63") (pinfunction "OSC1/CLKI/RC12_63") (pintype "bidirectional"))
      (node (ref "Y2") (pin "1") (pinfunction "1_1") (pintype "passive"))
    )
    (net (code "86") (name "Net-(U10-OSC2{slash}CLKO{slash}RC15)") (class "Default")
      (node (ref "C4") (pin "2") (pinfunction "2_2") (pintype "passive"))
      (node (ref "U10") (pin "64") (pinfunction "OSC2/CLKO/RC15_64") (pintype "bidirectional"))
      (node (ref "Y2") (pin "2") (pinfunction "2_2") (pintype "passive"))
    )
    (net (code "87") (name "Net-(U10-SOSCI{slash}CN1{slash}RC13)") (class "Default")
      (node (ref "C34") (pin "2") (pinfunction "2_2") (pintype "passive"))
      (node (ref "U10") (pin "73") (pinfunction "SOSCI/CN1/RC13_73") (pintype "bidirectional"))
      (node (ref "Y1") (pin "1") (pinfunction "1_1") (pintype "passive"))
    )
    (net (code "88") (name "Net-(U10-SOSCO{slash}T1CK{slash}CN0{slash}RC14)") (class "Default")
      (node (ref "C35") (pin "2") (pinfunction "2_2") (pintype "passive"))
      (node (ref "U10") (pin "74") (pinfunction "SOSCO/T1CK/CN0/RC14_74") (pintype "bidirectional"))
      (node (ref "Y1") (pin "2") (pinfunction "2_2") (pintype "passive"))
    )
    (net (code "89") (name "Net-(U10-VCAP{slash}VDDCORE)") (class "Default")
      (node (ref "C3") (pin "1") (pinfunction "1_1") (pintype "passive"))
      (node (ref "U10") (pin "85") (pinfunction "VCAP/VDDCORE_85") (pintype "power_in"))
    )
    (net (code "90") (name "VCC_32") (class "Default")
      (node (ref "C27") (pin "2") (pinfunction "2_2") (pintype "passive"))
      (node (ref "C28") (pin "2") (pinfunction "2_2") (pintype "passive"))
      (node (ref "C29") (pin "2") (pinfunction "2_2") (pintype "passive"))
      (node (ref "C30") (pin "2") (pinfunction "2_2") (pintype "passive"))
      (node (ref "C31") (pin "2") (pinfunction "2_2") (pintype "passive"))
      (node (ref "C32") (pin "2") (pinfunction "2_2") (pintype "passive"))
      (node (ref "C33") (pin "2") (pinfunction "2_2") (pintype "passive"))
      (node (ref "D12") (pin "1") (pinfunction "K1_1") (pintype "passive"))
      (node (ref "D12") (pin "2") (pinfunction "K2_2") (pintype "passive"))
      (node (ref "D14") (pin "1") (pinfunction "K1_1") (pintype "passive"))
      (node (ref "D14") (pin "2") (pinfunction "K2_2") (pintype "passive"))
      (node (ref "R75") (pin "2") (pinfunction "2_2") (pintype "passive"))
      (node (ref "U10") (pin "16") (pinfunction "VDD_16") (pintype "power_in"))
      (node (ref "U10") (pin "2") (pinfunction "VDD_2") (pintype "power_in"))
      (node (ref "U10") (pin "30") (pinfunction "AVDD_30") (pintype "power_in"))
      (node (ref "U10") (pin "37") (pinfunction "VDD_37") (pintype "power_in"))
      (node (ref "U10") (pin "46") (pinfunction "VDD_46") (pintype "power_in"))
      (node (ref "U10") (pin "55") (pinfunction "VUSB_55") (pintype "power_in"))
      (node (ref "U10") (pin "62") (pinfunction "VDD_62") (pintype "power_in"))
      (node (ref "U10") (pin "86") (pinfunction "VDD_86") (pintype "power_in"))
    )
    (net (code "91") (name "unconnected-(P10-Pad6)") (class "Default")
      (node (ref "P10") (pin "6") (pinfunction "6_6") (pintype "passive+no_connect"))
    )
    (net (code "92") (name "unconnected-(P15-LVP-Pad6)") (class "Default")
      (node (ref "P15") (pin "6") (pinfunction "LVP_6") (pintype "passive+no_connect"))
    )
    (net (code "93") (name "unconnected-(U10-AN5{slash}C1IN+{slash}VBUSON{slash}CN7{slash}RB5-Pad20)") (class "Default")
      (node (ref "U10") (pin "20") (pinfunction "AN5/C1IN+/VBUSON/CN7/RB5_20") (pintype "bidirectional+no_connect"))
    )
    (net (code "94") (name "unconnected-(U10-C1RX{slash}ETXD1{slash}PMD11{slash}RF0-Pad87)") (class "Default")
      (node (ref "U10") (pin "87") (pinfunction "C1RX/ETXD1/PMD11/RF0_87") (pintype "bidirectional+no_connect"))
    )
    (net (code "95") (name "unconnected-(U10-C1TX{slash}ETXD0{slash}PMD10{slash}RF1-Pad88)") (class "Default")
      (node (ref "U10") (pin "88") (pinfunction "C1TX/ETXD0/PMD10/RF1_88") (pintype "bidirectional+no_connect"))
    )
    (net (code "96") (name "unconnected-(U10-C2TX{slash}ETXERR{slash}PMD9{slash}RG1-Pad89)") (class "Default")
      (node (ref "U10") (pin "89") (pinfunction "C2TX/ETXERR/PMD9/RG1_89") (pintype "bidirectional+no_connect"))
    )
    (net (code "97") (name "unconnected-(U10-ECOL{slash}SCK2A{slash}U2BTX{slash}~{U2ARTS}{slash}PMA5{slash}CN8{slash}RG6-Pad10)") (class "Default")
      (node (ref "U10") (pin "10") (pinfunction "ECOL/SCK2A/U2BTX/~{U2ARTS}/PMA5/CN8/RG6_10") (pintype "bidirectional"))
    )
    (net (code "98") (name "unconnected-(U10-ECRS{slash}SDA2A{slash}SDI2A{slash}U2ARX{slash}PMA4{slash}CN9{slash}RG7-Pad11)") (class "Default")
      (node (ref "U10") (pin "11") (pinfunction "ECRS/SDA2A/SDI2A/U2ARX/PMA4/CN9/RG7_11") (pintype "bidirectional+no_connect"))
    )
    (net (code "99") (name "unconnected-(U10-ETXCLK{slash}PMD15{slash}CN16{slash}RD7-Pad84)") (class "Default")
      (node (ref "U10") (pin "84") (pinfunction "ETXCLK/PMD15/CN16/RD7_84") (pintype "bidirectional"))
    )
    (net (code "100") (name "unconnected-(U10-ETXD2{slash}IC5{slash}PMD12{slash}RD12-Pad79)") (class "Default")
      (node (ref "U10") (pin "79") (pinfunction "ETXD2/IC5/PMD12/RD12_79") (pintype "bidirectional"))
    )
    (net (code "101") (name "unconnected-(U10-ETXD3{slash}PMD13{slash}CN19{slash}RD13-Pad80)") (class "Default")
      (node (ref "U10") (pin "80") (pinfunction "ETXD3/PMD13/CN19/RD13_80") (pintype "bidirectional"))
    )
    (net (code "102") (name "unconnected-(U10-ETXEN{slash}PMD14{slash}CN15{slash}RD6-Pad83)") (class "Default")
      (node (ref "U10") (pin "83") (pinfunction "ETXEN/PMD14/CN15/RD6_83") (pintype "bidirectional"))
    )
    (net (code "103") (name "unconnected-(U10-OC3{slash}RD2-Pad77)") (class "Default")
      (node (ref "U10") (pin "77") (pinfunction "OC3/RD2_77") (pintype "bidirectional"))
    )
    (net (code "104") (name "unconnected-(U10-OC4{slash}RD3-Pad78)") (class "Default")
      (node (ref "U10") (pin "78") (pinfunction "OC4/RD3_78") (pintype "bidirectional"))
    )
    (net (code "105") (name "unconnected-(U10-OC5{slash}PMWR{slash}CN13{slash}RD4-Pad81)") (class "Default")
      (node (ref "U10") (pin "81") (pinfunction "OC5/PMWR/CN13/RD4_81") (pintype "bidirectional"))
    )
    (net (code "106") (name "unconnected-(U10-PGED2{slash}AN7{slash}RB7-Pad27)") (class "Default")
      (node (ref "U10") (pin "27") (pinfunction "PGED2/AN7/RB7_27") (pintype "bidirectional"))
    )
    (net (code "107") (name "unconnected-(U10-PMD0{slash}RE0-Pad93)") (class "Default")
      (node (ref "U10") (pin "93") (pinfunction "PMD0/RE0_93") (pintype "bidirectional"))
    )
    (net (code "108") (name "unconnected-(U10-PMRD{slash}CN14{slash}RD5-Pad82)") (class "Default")
      (node (ref "U10") (pin "82") (pinfunction "PMRD/CN14/RD5_82") (pintype "bidirectional"))
    )
    (net (code "109") (name "unconnected-(U10-SCK1{slash}IC3{slash}PMCS2{slash}PMA15{slash}RD10-Pad70)") (class "Default")
      (node (ref "U10") (pin "70") (pinfunction "SCK1/IC3/PMCS2/PMA15/RD10_70") (pintype "bidirectional"))
    )
    (net (code "110") (name "unconnected-(U10-T3CK{slash}AC2TX{slash}RC2-Pad7)") (class "Default")
      (node (ref "U10") (pin "7") (pinfunction "T3CK/AC2TX/RC2_7") (pintype "bidirectional"))
    )
    (net (code "111") (name "unconnected-(U10-T4CK{slash}AC2RX{slash}RC3-Pad8)") (class "Default")
      (node (ref "U10") (pin "8") (pinfunction "T4CK/AC2RX/RC3_8") (pintype "bidirectional"))
    )
    (net (code "112") (name "unconnected-(U10-T5CK{slash}SDI1{slash}RC4-Pad9)") (class "Default")
      (node (ref "U10") (pin "9") (pinfunction "T5CK/SDI1/RC4_9") (pintype "bidirectional"))
    )
    (net (code "113") (name "unconnected-(U10-TCK{slash}RA1-Pad38)") (class "Default")
      (node (ref "U10") (pin "38") (pinfunction "TCK/RA1_38") (pintype "bidirectional"))
    )
    (net (code "114") (name "unconnected-(U10-TDI{slash}RA4-Pad60)") (class "Default")
      (node (ref "U10") (pin "60") (pinfunction "TDI/RA4_60") (pintype "bidirectional"))
    )
    (net (code "115") (name "unconnected-(U10-TDO{slash}RA5-Pad61)") (class "Default")
      (node (ref "U10") (pin "61") (pinfunction "TDO/RA5_61") (pintype "bidirectional"))
    )
    (net (code "116") (name "unconnected-(U10-TMS{slash}RA0-Pad17)") (class "Default")
      (node (ref "U10") (pin "17") (pinfunction "TMS/RA0_17") (pintype "bidirectional"))
    )
    (net (code "117") (name "unconnected-(U10-USBID{slash}RF3-Pad51)") (class "Default")
      (node (ref "U10") (pin "51") (pinfunction "USBID/RF3_51") (pintype "bidirectional+no_connect"))
    )
    (net (code "118") (name "unconnected-(U10-VREF+{slash}CVREF+{slash}AERXD3{slash}PMA6{slash}RA10-Pad29)") (class "Default")
      (node (ref "U10") (pin "29") (pinfunction "VREF+/CVREF+/AERXD3/PMA6/RA10_29") (pintype "bidirectional"))
    )
    (net (code "119") (name "unconnected-(U10-VREF-{slash}CVREF-{slash}AERXD2{slash}PMA7{slash}RA9-Pad28)") (class "Default")
      (node (ref "U10") (pin "28") (pinfunction "VREF-/CVREF-/AERXD2/PMA7/RA9_28") (pintype "bidirectional"))
    )
    (net (code "120") (name "unconnected-(U10-~{SS1}{slash}IC2{slash}RD9-Pad69)") (class "Default")
      (node (ref "U10") (pin "69") (pinfunction "~{SS1}/IC2/RD9_69") (pintype "bidirectional"))
    )
  )
)
